# Squirco_Logic_v1_0.net
KiCad netlist of a schematic drawn in EAGLE
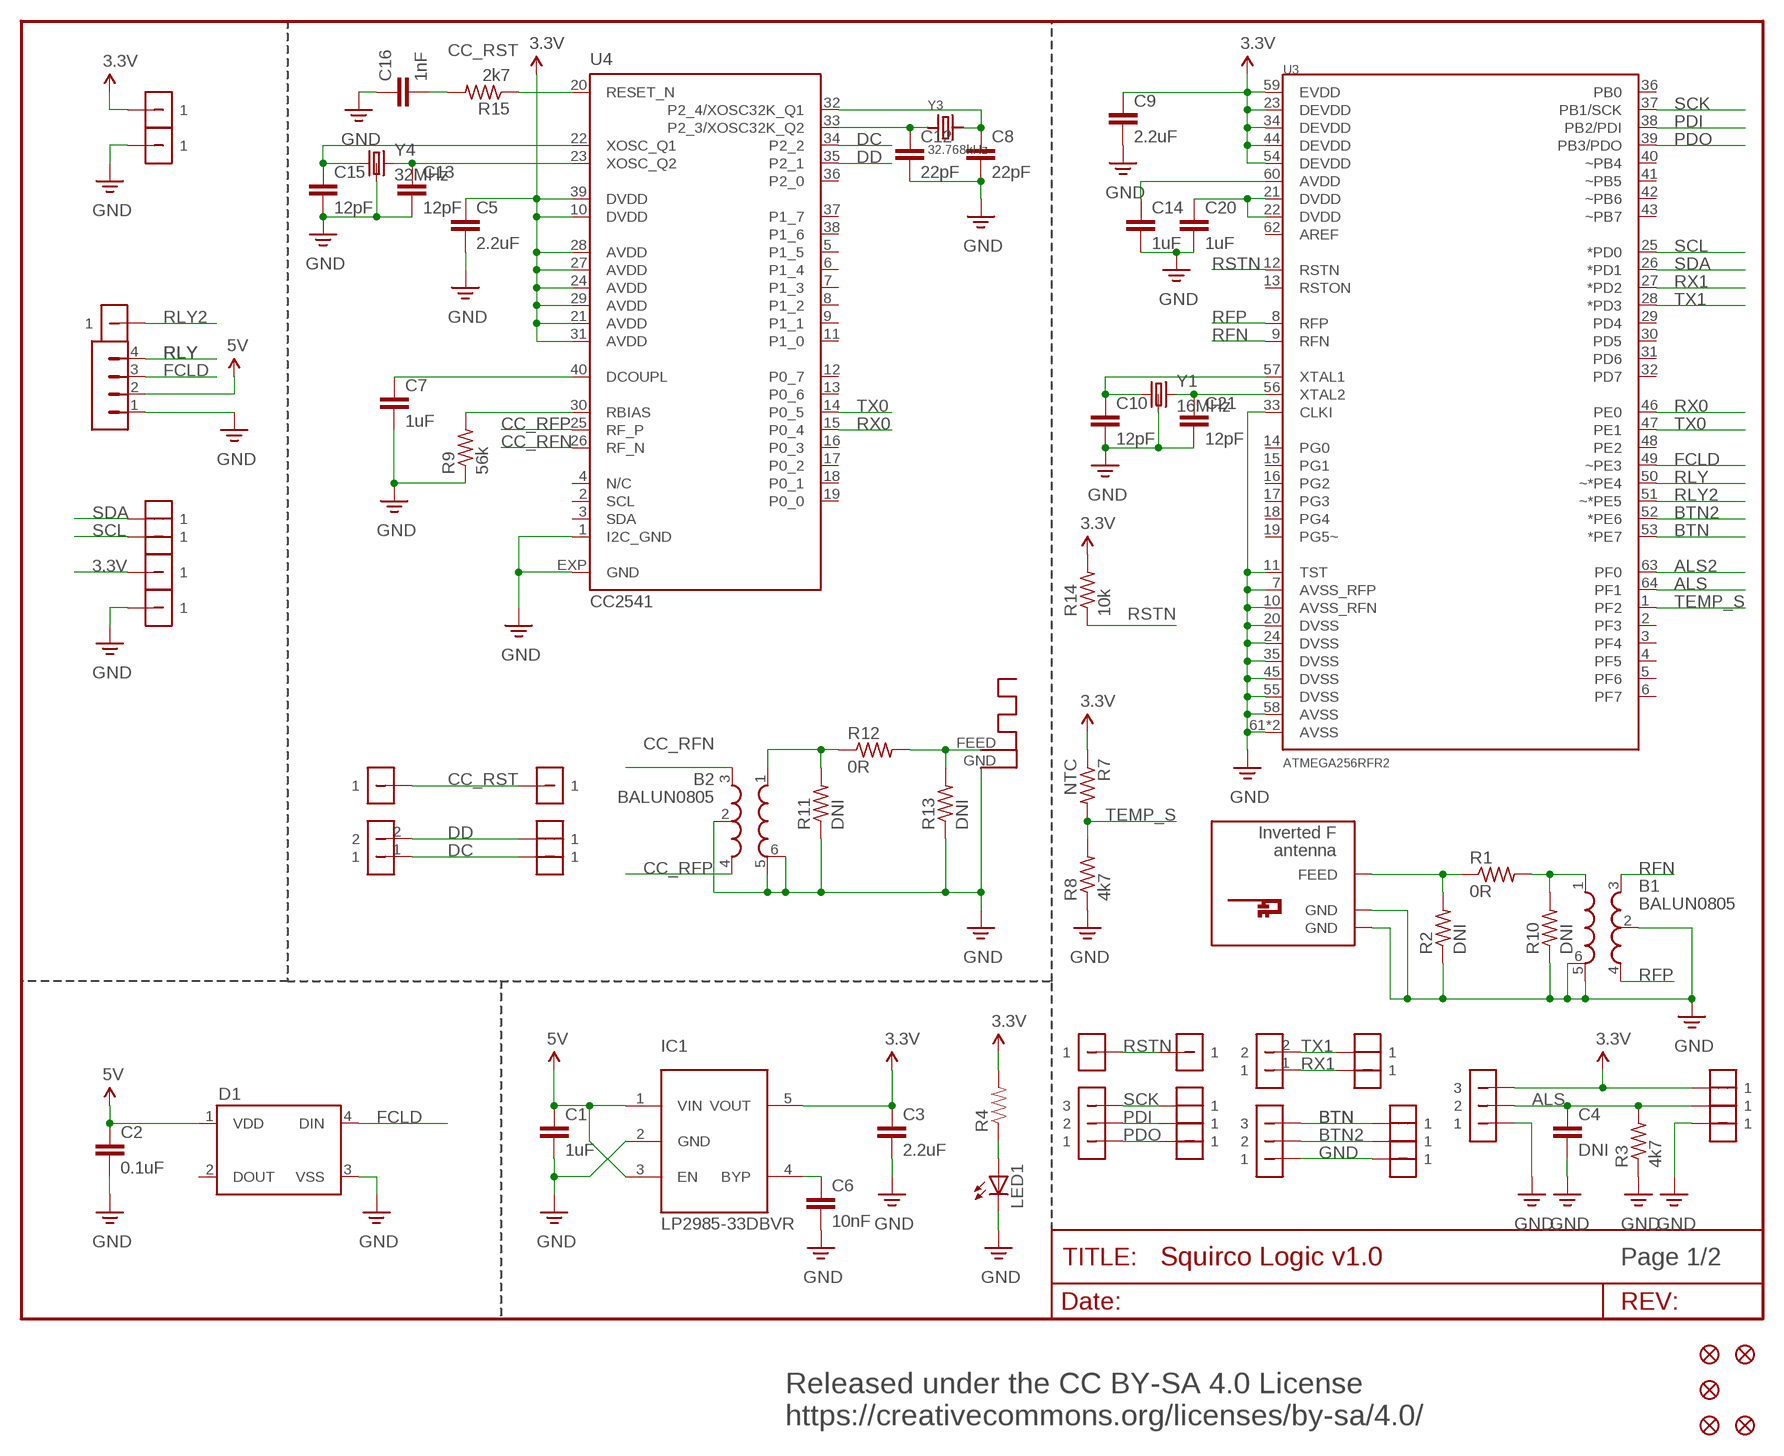
[diagram p0: schematic, sheet 1]

(export (version "E")
  (design (tool "Eeschema 10.0.6"))
  (components
    (comp (ref "ANT1")
      (value "ANTENNA")
      (footprint "eagle-import:RN-ANT")
      (libsource (lib "eagle-import") (part "ANTENNA"))
    )
    (comp (ref "ANT2")
      (value "INVERTED_F_ANTENNA+5")
      (footprint "eagle-import:DN007+5")
      (libsource (lib "eagle-import") (part "INVERTED_F_ANTENNA+5"))
    )
    (comp (ref "B1")
      (value "BALUN0805")
      (footprint "eagle-import:BALUN-2-4GHZ")
      (libsource (lib "eagle-import") (part "BALUN0805"))
    )
    (comp (ref "B2")
      (value "BALUN0805")
      (footprint "eagle-import:BALUN-2-4GHZ")
      (libsource (lib "eagle-import") (part "BALUN0805"))
    )
    (comp (ref "C1")
      (value "1uF")
      (footprint "eagle-import:0603-CAP")
      (libsource (lib "eagle-import") (part "CAP0603-CAP"))
    )
    (comp (ref "C2")
      (value "0.1uF")
      (footprint "eagle-import:0603-CAP")
      (libsource (lib "eagle-import") (part "CAP0603-CAP"))
    )
    (comp (ref "C3")
      (value "2.2uF")
      (footprint "eagle-import:0603-CAP")
      (libsource (lib "eagle-import") (part "CAP0603-CAP"))
    )
    (comp (ref "C4")
      (value "DNI")
      (footprint "eagle-import:0603-CAP")
      (libsource (lib "eagle-import") (part "CAP0603-CAP"))
    )
    (comp (ref "C5")
      (value "2.2uF")
      (footprint "eagle-import:0603-CAP")
      (libsource (lib "eagle-import") (part "CAP0603-CAP"))
    )
    (comp (ref "C6")
      (value "10nF")
      (footprint "eagle-import:0603-CAP")
      (libsource (lib "eagle-import") (part "CAP0603-CAP"))
    )
    (comp (ref "C7")
      (value "1uF")
      (footprint "eagle-import:0603-CAP")
      (libsource (lib "eagle-import") (part "CAP0603-CAP"))
    )
    (comp (ref "C8")
      (value "22pF")
      (footprint "eagle-import:0402-CAP")
      (libsource (lib "eagle-import") (part "CAP0402-CAP"))
    )
    (comp (ref "C9")
      (value "2.2uF")
      (footprint "eagle-import:0603-CAP")
      (libsource (lib "eagle-import") (part "CAP0603-CAP"))
    )
    (comp (ref "C10")
      (value "12pF")
      (footprint "eagle-import:0402-CAP")
      (libsource (lib "eagle-import") (part "CAP0402-CAP"))
    )
    (comp (ref "C12")
      (value "22pF")
      (footprint "eagle-import:0402-CAP")
      (libsource (lib "eagle-import") (part "CAP0402-CAP"))
    )
    (comp (ref "C13")
      (value "12pF")
      (footprint "eagle-import:0402-CAP")
      (libsource (lib "eagle-import") (part "CAP0402-CAP"))
    )
    (comp (ref "C14")
      (value "1uF")
      (footprint "eagle-import:0603-CAP")
      (libsource (lib "eagle-import") (part "CAP0603-CAP"))
    )
    (comp (ref "C15")
      (value "12pF")
      (footprint "eagle-import:0402-CAP")
      (libsource (lib "eagle-import") (part "CAP0402-CAP"))
    )
    (comp (ref "C16")
      (value "1nF")
      (footprint "eagle-import:0603-CAP")
      (libsource (lib "eagle-import") (part "CAP0603-CAP"))
    )
    (comp (ref "C20")
      (value "1uF")
      (footprint "eagle-import:0603-CAP")
      (libsource (lib "eagle-import") (part "CAP0603-CAP"))
    )
    (comp (ref "C21")
      (value "12pF")
      (footprint "eagle-import:0402-CAP")
      (libsource (lib "eagle-import") (part "CAP0402-CAP"))
    )
    (comp (ref "D1")
      (value "WS2812B")
      (footprint "eagle-import:WS2812B")
      (libsource (lib "eagle-import") (part "WS2812B"))
    )
    (comp (ref "FID1")
      (value "FIDUCIALUFIDUCIAL")
      (footprint "eagle-import:MICRO-FIDUCIAL")
      (libsource (lib "eagle-import") (part "FIDUCIALUFIDUCIAL"))
    )
    (comp (ref "FID2")
      (value "FIDUCIALUFIDUCIAL")
      (footprint "eagle-import:MICRO-FIDUCIAL")
      (libsource (lib "eagle-import") (part "FIDUCIALUFIDUCIAL"))
    )
    (comp (ref "FID3")
      (value "FIDUCIALUFIDUCIAL")
      (footprint "eagle-import:MICRO-FIDUCIAL")
      (libsource (lib "eagle-import") (part "FIDUCIALUFIDUCIAL"))
    )
    (comp (ref "FID5")
      (value "FIDUCIALUFIDUCIAL")
      (footprint "eagle-import:MICRO-FIDUCIAL")
      (libsource (lib "eagle-import") (part "FIDUCIALUFIDUCIAL"))
    )
    (comp (ref "FID6")
      (value "FIDUCIALUFIDUCIAL")
      (footprint "eagle-import:MICRO-FIDUCIAL")
      (libsource (lib "eagle-import") (part "FIDUCIALUFIDUCIAL"))
    )
    (comp (ref "IC1")
      (value "LP2985-33DBVR")
      (footprint "eagle-import:SOT23-5L")
      (libsource (lib "eagle-import") (part "LP298XS"))
    )
    (comp (ref "JP1")
      (value "M02")
      (footprint "eagle-import:M02")
      (libsource (lib "eagle-import") (part "M02"))
    )
    (comp (ref "LED1")
      (value "LEDCHIP-LED0805")
      (footprint "eagle-import:CHIP-LED0805")
      (libsource (lib "eagle-import") (part "LEDCHIP-LED0805"))
    )
    (comp (ref "R1")
      (value "0R")
      (footprint "eagle-import:R0402")
      (libsource (lib "eagle-import") (part "R-US_R0402"))
    )
    (comp (ref "R2")
      (value "DNI")
      (footprint "eagle-import:R0402")
      (libsource (lib "eagle-import") (part "R-US_R0402"))
    )
    (comp (ref "R3")
      (value "4k7")
      (footprint "eagle-import:R0603")
      (libsource (lib "eagle-import") (part "R-US_R0603"))
    )
    (comp (ref "R4")
      (value "RESISTOR0603")
      (footprint "eagle-import:0603-RES")
      (libsource (lib "eagle-import") (part "RESISTOR0603"))
    )
    (comp (ref "R7")
      (value "NTC")
      (footprint "eagle-import:R0402")
      (libsource (lib "eagle-import") (part "R-US_R0402"))
    )
    (comp (ref "R8")
      (value "4k7")
      (footprint "eagle-import:R0603")
      (libsource (lib "eagle-import") (part "R-US_R0603"))
    )
    (comp (ref "R9")
      (value "56k")
      (footprint "eagle-import:R0603")
      (libsource (lib "eagle-import") (part "R-US_R0603"))
    )
    (comp (ref "R10")
      (value "DNI")
      (footprint "eagle-import:R0402")
      (libsource (lib "eagle-import") (part "R-US_R0402"))
    )
    (comp (ref "R11")
      (value "DNI")
      (footprint "eagle-import:R0402")
      (libsource (lib "eagle-import") (part "R-US_R0402"))
    )
    (comp (ref "R12")
      (value "0R")
      (footprint "eagle-import:R0402")
      (libsource (lib "eagle-import") (part "R-US_R0402"))
    )
    (comp (ref "R13")
      (value "DNI")
      (footprint "eagle-import:R0402")
      (libsource (lib "eagle-import") (part "R-US_R0402"))
    )
    (comp (ref "R14")
      (value "10k")
      (footprint "eagle-import:R0603")
      (libsource (lib "eagle-import") (part "R-US_R0603"))
    )
    (comp (ref "R15")
      (value "2k7")
      (footprint "eagle-import:R0603")
      (libsource (lib "eagle-import") (part "R-US_R0603"))
    )
    (comp (ref "U$4")
      (value "M03")
      (footprint "eagle-import:M03")
      (libsource (lib "eagle-import") (part "M03"))
    )
    (comp (ref "U$5")
      (value "S04-4MM")
      (footprint "eagle-import:S04-4MM")
      (libsource (lib "eagle-import") (part "S04-4MM"))
    )
    (comp (ref "U$6")
      (value "M03")
      (footprint "eagle-import:M03")
      (libsource (lib "eagle-import") (part "M03"))
    )
    (comp (ref "U$7")
      (value "M01")
      (footprint "eagle-import:M01")
      (libsource (lib "eagle-import") (part "M01"))
    )
    (comp (ref "U$8")
      (value "M01")
      (footprint "eagle-import:M01")
      (libsource (lib "eagle-import") (part "M01"))
    )
    (comp (ref "U$9")
      (value "M02")
      (footprint "eagle-import:M02")
      (libsource (lib "eagle-import") (part "M02"))
    )
    (comp (ref "U$10")
      (value "S01C-4MM")
      (footprint "eagle-import:S01C-4MM")
      (libsource (lib "eagle-import") (part "S01C-4MM"))
    )
    (comp (ref "U$11")
      (value "S01C-4MM")
      (footprint "eagle-import:S01C-4MM")
      (libsource (lib "eagle-import") (part "S01C-4MM"))
    )
    (comp (ref "U$12")
      (value "S01C-4MM")
      (footprint "eagle-import:S01C-4MM")
      (libsource (lib "eagle-import") (part "S01C-4MM"))
    )
    (comp (ref "U$13")
      (value "S01C-4MM")
      (footprint "eagle-import:S01C-4MM")
      (libsource (lib "eagle-import") (part "S01C-4MM"))
    )
    (comp (ref "U$14")
      (value "S01C-4MM")
      (footprint "eagle-import:S01C-4MM")
      (libsource (lib "eagle-import") (part "S01C-4MM"))
    )
    (comp (ref "U$15")
      (value "S01C-4MM")
      (footprint "eagle-import:S01C-4MM")
      (libsource (lib "eagle-import") (part "S01C-4MM"))
    )
    (comp (ref "U$16")
      (value "S01C-4MM")
      (footprint "eagle-import:S01C-4MM")
      (libsource (lib "eagle-import") (part "S01C-4MM"))
    )
    (comp (ref "U$17")
      (value "S01C-4MM")
      (footprint "eagle-import:S01C-4MM")
      (libsource (lib "eagle-import") (part "S01C-4MM"))
    )
    (comp (ref "U$18")
      (value "S01C-4MM")
      (footprint "eagle-import:S01C-4MM")
      (libsource (lib "eagle-import") (part "S01C-4MM"))
    )
    (comp (ref "U$19")
      (value "S01C-4MM")
      (footprint "eagle-import:S01C-4MM")
      (libsource (lib "eagle-import") (part "S01C-4MM"))
    )
    (comp (ref "U$20")
      (value "S01C-4MM")
      (footprint "eagle-import:S01C-4MM")
      (libsource (lib "eagle-import") (part "S01C-4MM"))
    )
    (comp (ref "U$21")
      (value "S01C-4MM")
      (footprint "eagle-import:S01C-4MM")
      (libsource (lib "eagle-import") (part "S01C-4MM"))
    )
    (comp (ref "U$22")
      (value "S01C-4MM")
      (footprint "eagle-import:S01C-4MM")
      (libsource (lib "eagle-import") (part "S01C-4MM"))
    )
    (comp (ref "U$23")
      (value "S01C-4MM")
      (footprint "eagle-import:S01C-4MM")
      (libsource (lib "eagle-import") (part "S01C-4MM"))
    )
    (comp (ref "U$24")
      (value "S01C-4MM")
      (footprint "eagle-import:S01C-4MM")
      (libsource (lib "eagle-import") (part "S01C-4MM"))
    )
    (comp (ref "U$25")
      (value "M03")
      (footprint "eagle-import:M03")
      (libsource (lib "eagle-import") (part "M03"))
    )
    (comp (ref "U$26")
      (value "S01C-4MM")
      (footprint "eagle-import:S01C-4MM")
      (libsource (lib "eagle-import") (part "S01C-4MM"))
    )
    (comp (ref "U$27")
      (value "S01C-4MM")
      (footprint "eagle-import:S01C-4MM")
      (libsource (lib "eagle-import") (part "S01C-4MM"))
    )
    (comp (ref "U$30")
      (value "S01C-4MM")
      (footprint "eagle-import:S01C-4MM")
      (libsource (lib "eagle-import") (part "S01C-4MM"))
    )
    (comp (ref "U$31")
      (value "S01C-4MM")
      (footprint "eagle-import:S01C-4MM")
      (libsource (lib "eagle-import") (part "S01C-4MM"))
    )
    (comp (ref "U$32")
      (value "S01-4MM")
      (footprint "eagle-import:S01-4MM")
      (libsource (lib "eagle-import") (part "S01-4MM"))
    )
    (comp (ref "U$33")
      (value "S01-4MM")
      (footprint "eagle-import:S01-4MM")
      (libsource (lib "eagle-import") (part "S01-4MM"))
    )
    (comp (ref "U$34")
      (value "S01C-4MM")
      (footprint "eagle-import:S01C-4MM")
      (libsource (lib "eagle-import") (part "S01C-4MM"))
    )
    (comp (ref "U3")
      (value "ATMEGA256RFR2")
      (footprint "eagle-import:QFN-64")
      (libsource (lib "eagle-import") (part "ATMEGA256RFR2"))
    )
    (comp (ref "U4")
      (value "CC2541")
      (footprint "eagle-import:RHA_S-PVQFN-N40")
      (libsource (lib "eagle-import") (part "CC2541"))
    )
    (comp (ref "Y1")
      (value "16MHz")
      (footprint "eagle-import:CRYSTAL-SMD-2.5X2-ABM10")
      (libsource (lib "eagle-import") (part "CRYSTALABM10"))
    )
    (comp (ref "Y3")
      (value "32.768kHz")
      (footprint "eagle-import:ABS07")
      (libsource (lib "eagle-import") (part "CRYSTAL.ABS07"))
    )
    (comp (ref "Y4")
      (value "32MHz")
      (footprint "eagle-import:CRYSTAL-SMD-2.5X2-ABM10")
      (libsource (lib "eagle-import") (part "CRYSTALABM10"))
    )
  )
  (nets
    (net (code "1") (name "/ALS") (class "Default")
      (node (ref "C4") (pin "1") (pinfunction "1_1") (pintype "passive"))
      (node (ref "R3") (pin "2") (pinfunction "2_2") (pintype "passive"))
      (node (ref "U$25") (pin "2") (pinfunction "2_2") (pintype "bidirectional"))
      (node (ref "U$31") (pin "P$1") (pinfunction "1_P$1") (pintype "bidirectional"))
      (node (ref "U3") (pin "64") (pinfunction "PF1_64") (pintype "bidirectional"))
    )
    (net (code "2") (name "/ALS2") (class "Default")
      (node (ref "U3") (pin "63") (pinfunction "PF0_63") (pintype "bidirectional"))
    )
    (net (code "3") (name "/BTN") (class "Default")
      (node (ref "U$22") (pin "P$1") (pinfunction "1_P$1") (pintype "bidirectional"))
      (node (ref "U$6") (pin "3") (pinfunction "3_3") (pintype "bidirectional"))
      (node (ref "U3") (pin "53") (pinfunction "*PE7_53") (pintype "bidirectional"))
    )
    (net (code "4") (name "/BTN2") (class "Default")
      (node (ref "U$23") (pin "P$1") (pinfunction "1_P$1") (pintype "bidirectional"))
      (node (ref "U$6") (pin "2") (pinfunction "2_2") (pintype "bidirectional"))
      (node (ref "U3") (pin "52") (pinfunction "*PE6_52") (pintype "bidirectional"))
    )
    (net (code "5") (name "/CC_RFN") (class "Default")
      (node (ref "B2") (pin "3") (pinfunction "3_3") (pintype "bidirectional"))
      (node (ref "U4") (pin "26") (pinfunction "RF_N_26") (pintype "bidirectional"))
    )
    (net (code "6") (name "/CC_RFP") (class "Default")
      (node (ref "B2") (pin "4") (pinfunction "4_4") (pintype "bidirectional"))
      (node (ref "U4") (pin "25") (pinfunction "RF_P_25") (pintype "bidirectional"))
    )
    (net (code "7") (name "/CC_RST") (class "Default")
      (node (ref "C16") (pin "2") (pinfunction "2_2") (pintype "passive"))
      (node (ref "R15") (pin "2") (pinfunction "2_2") (pintype "passive"))
      (node (ref "U$17") (pin "P$1") (pinfunction "1_P$1") (pintype "bidirectional"))
      (node (ref "U$8") (pin "1") (pinfunction "1_1") (pintype "bidirectional"))
    )
    (net (code "8") (name "/DC") (class "Default")
      (node (ref "U$19") (pin "P$1") (pinfunction "1_P$1") (pintype "bidirectional"))
      (node (ref "U$9") (pin "1") (pinfunction "1_1") (pintype "bidirectional"))
      (node (ref "U4") (pin "34") (pinfunction "P2_2_34") (pintype "bidirectional"))
    )
    (net (code "9") (name "/DD") (class "Default")
      (node (ref "U$18") (pin "P$1") (pinfunction "1_P$1") (pintype "bidirectional"))
      (node (ref "U$9") (pin "2") (pinfunction "2_2") (pintype "bidirectional"))
      (node (ref "U4") (pin "35") (pinfunction "P2_1_35") (pintype "bidirectional"))
    )
    (net (code "10") (name "/FCLD") (class "Default")
      (node (ref "D1") (pin "4") (pinfunction "DIN_4") (pintype "input"))
      (node (ref "U$5") (pin "3") (pinfunction "3_3") (pintype "bidirectional"))
      (node (ref "U3") (pin "49") (pinfunction "~{PE3}_49") (pintype "bidirectional"))
    )
    (net (code "11") (name "/N{slash}C") (class "Default")
      (node (ref "U4") (pin "4") (pinfunction "N/C_4") (pintype "power_in"))
    )
    (net (code "12") (name "/PDI") (class "Default")
      (node (ref "U$13") (pin "P$1") (pinfunction "1_P$1") (pintype "bidirectional"))
      (node (ref "U$4") (pin "2") (pinfunction "2_2") (pintype "bidirectional"))
      (node (ref "U3") (pin "38") (pinfunction "PB2/PDI_38") (pintype "bidirectional"))
    )
    (net (code "13") (name "/PDO") (class "Default")
      (node (ref "U$14") (pin "P$1") (pinfunction "1_P$1") (pintype "bidirectional"))
      (node (ref "U$4") (pin "1") (pinfunction "1_1") (pintype "bidirectional"))
      (node (ref "U3") (pin "39") (pinfunction "PB3/PDO_39") (pintype "bidirectional"))
    )
    (net (code "14") (name "/RFN") (class "Default")
      (node (ref "B1") (pin "3") (pinfunction "3_3") (pintype "bidirectional"))
      (node (ref "U3") (pin "9") (pinfunction "RFN_9") (pintype "bidirectional"))
    )
    (net (code "15") (name "/RFP") (class "Default")
      (node (ref "B1") (pin "4") (pinfunction "4_4") (pintype "bidirectional"))
      (node (ref "U3") (pin "8") (pinfunction "RFP_8") (pintype "bidirectional"))
    )
    (net (code "16") (name "/RLY") (class "Default")
      (node (ref "U$5") (pin "4") (pinfunction "4_4") (pintype "bidirectional"))
      (node (ref "U3") (pin "50") (pinfunction "~{*PE4}_50") (pintype "bidirectional"))
    )
    (net (code "17") (name "/RLY2") (class "Default")
      (node (ref "U$34") (pin "P$1") (pinfunction "1_P$1") (pintype "bidirectional"))
      (node (ref "U3") (pin "51") (pinfunction "~{*PE5}_51") (pintype "bidirectional"))
    )
    (net (code "18") (name "/RSTN") (class "Default")
      (node (ref "R14") (pin "1") (pinfunction "1_1") (pintype "passive"))
      (node (ref "U$11") (pin "P$1") (pinfunction "1_P$1") (pintype "bidirectional"))
      (node (ref "U$7") (pin "1") (pinfunction "1_1") (pintype "bidirectional"))
      (node (ref "U3") (pin "12") (pinfunction "RSTN_12") (pintype "bidirectional"))
    )
    (net (code "19") (name "/RX0") (class "Default")
      (node (ref "U3") (pin "46") (pinfunction "PE0_46") (pintype "bidirectional"))
      (node (ref "U4") (pin "15") (pinfunction "P0_4_15") (pintype "bidirectional"))
    )
    (net (code "20") (name "/RX1") (class "Default")
      (node (ref "JP1") (pin "1") (pinfunction "1_1") (pintype "bidirectional"))
      (node (ref "U$16") (pin "P$1") (pinfunction "1_P$1") (pintype "bidirectional"))
      (node (ref "U3") (pin "27") (pinfunction "*PD2_27") (pintype "bidirectional"))
    )
    (net (code "21") (name "/SCK") (class "Default")
      (node (ref "U$12") (pin "P$1") (pinfunction "1_P$1") (pintype "bidirectional"))
      (node (ref "U$4") (pin "3") (pinfunction "3_3") (pintype "bidirectional"))
      (node (ref "U3") (pin "37") (pinfunction "PB1/SCK_37") (pintype "bidirectional"))
    )
    (net (code "22") (name "/SCL") (class "Default")
      (node (ref "U$24") (pin "P$1") (pinfunction "1_P$1") (pintype "bidirectional"))
      (node (ref "U3") (pin "25") (pinfunction "*PD0_25") (pintype "bidirectional"))
    )
    (net (code "23") (name "/SDA") (class "Default")
      (node (ref "U$10") (pin "P$1") (pinfunction "1_P$1") (pintype "bidirectional"))
      (node (ref "U3") (pin "26") (pinfunction "*PD1_26") (pintype "bidirectional"))
    )
    (net (code "24") (name "/TEMP_S") (class "Default")
      (node (ref "R7") (pin "2") (pinfunction "2_2") (pintype "passive"))
      (node (ref "R8") (pin "2") (pinfunction "2_2") (pintype "passive"))
      (node (ref "U3") (pin "1") (pinfunction "PF2_1") (pintype "bidirectional"))
    )
    (net (code "25") (name "/TX0") (class "Default")
      (node (ref "U3") (pin "47") (pinfunction "PE1_47") (pintype "bidirectional"))
      (node (ref "U4") (pin "14") (pinfunction "P0_5_14") (pintype "bidirectional"))
    )
    (net (code "26") (name "/TX1") (class "Default")
      (node (ref "JP1") (pin "2") (pinfunction "2_2") (pintype "bidirectional"))
      (node (ref "U$15") (pin "P$1") (pinfunction "1_P$1") (pintype "bidirectional"))
      (node (ref "U3") (pin "28") (pinfunction "*PD3_28") (pintype "bidirectional"))
    )
    (net (code "27") (name "3.3V") (class "Default")
      (node (ref "C3") (pin "1") (pinfunction "1_1") (pintype "passive"))
      (node (ref "C5") (pin "1") (pinfunction "1_1") (pintype "passive"))
      (node (ref "C9") (pin "1") (pinfunction "1_1") (pintype "passive"))
      (node (ref "IC1") (pin "5") (pinfunction "VOUT_5") (pintype "bidirectional"))
      (node (ref "R14") (pin "2") (pinfunction "2_2") (pintype "passive"))
      (node (ref "R4") (pin "2") (pinfunction "2_2") (pintype "passive"))
      (node (ref "R7") (pin "1") (pinfunction "1_1") (pintype "passive"))
      (node (ref "U$20") (pin "P$1") (pinfunction "1_P$1") (pintype "bidirectional"))
      (node (ref "U$25") (pin "3") (pinfunction "3_3") (pintype "bidirectional"))
      (node (ref "U$26") (pin "P$1") (pinfunction "1_P$1") (pintype "bidirectional"))
      (node (ref "U$30") (pin "P$1") (pinfunction "1_P$1") (pintype "bidirectional"))
      (node (ref "U3") (pin "23") (pinfunction "DEVDD_23") (pintype "bidirectional"))
      (node (ref "U3") (pin "34") (pinfunction "DEVDD_34") (pintype "bidirectional"))
      (node (ref "U3") (pin "44") (pinfunction "DEVDD_44") (pintype "bidirectional"))
      (node (ref "U3") (pin "54") (pinfunction "DEVDD_54") (pintype "bidirectional"))
      (node (ref "U3") (pin "59") (pinfunction "EVDD_59") (pintype "bidirectional"))
      (node (ref "U4") (pin "10") (pinfunction "DVDD_10") (pintype "power_in"))
      (node (ref "U4") (pin "21") (pinfunction "AVDD_21") (pintype "power_in"))
      (node (ref "U4") (pin "24") (pinfunction "AVDD_24") (pintype "power_in"))
      (node (ref "U4") (pin "27") (pinfunction "AVDD_27") (pintype "power_in"))
      (node (ref "U4") (pin "28") (pinfunction "AVDD_28") (pintype "power_in"))
      (node (ref "U4") (pin "29") (pinfunction "AVDD_29") (pintype "power_in"))
      (node (ref "U4") (pin "31") (pinfunction "AVDD_31") (pintype "power_in"))
      (node (ref "U4") (pin "39") (pinfunction "DVDD_39") (pintype "power_in"))
    )
    (net (code "28") (name "5V") (class "Default")
      (node (ref "C1") (pin "1") (pinfunction "1_1") (pintype "passive"))
      (node (ref "C2") (pin "1") (pinfunction "1_1") (pintype "passive"))
      (node (ref "D1") (pin "1") (pinfunction "VDD_1") (pintype "power_in"))
      (node (ref "IC1") (pin "1") (pinfunction "VIN_1") (pintype "bidirectional"))
      (node (ref "IC1") (pin "3") (pinfunction "EN_3") (pintype "bidirectional"))
      (node (ref "U$5") (pin "2") (pinfunction "2_2") (pintype "bidirectional"))
    )
    (net (code "29") (name "GND") (class "Default")
      (node (ref "ANT1") (pin "GND") (pinfunction "GND_GND") (pintype "passive"))
      (node (ref "ANT2") (pin "GND") (pinfunction "GND_GND") (pintype "bidirectional"))
      (node (ref "ANT2") (pin "GND@1") (pinfunction "GND_GND@1") (pintype "bidirectional"))
      (node (ref "B1") (pin "2") (pinfunction "2_2") (pintype "bidirectional"))
      (node (ref "B1") (pin "5") (pinfunction "5_5") (pintype "bidirectional"))
      (node (ref "B1") (pin "6") (pinfunction "6_6") (pintype "bidirectional"))
      (node (ref "B2") (pin "2") (pinfunction "2_2") (pintype "bidirectional"))
      (node (ref "B2") (pin "5") (pinfunction "5_5") (pintype "bidirectional"))
      (node (ref "B2") (pin "6") (pinfunction "6_6") (pintype "bidirectional"))
      (node (ref "C1") (pin "2") (pinfunction "2_2") (pintype "passive"))
      (node (ref "C10") (pin "2") (pinfunction "2_2") (pintype "passive"))
      (node (ref "C12") (pin "2") (pinfunction "2_2") (pintype "passive"))
      (node (ref "C13") (pin "2") (pinfunction "2_2") (pintype "passive"))
      (node (ref "C14") (pin "2") (pinfunction "2_2") (pintype "passive"))
      (node (ref "C15") (pin "2") (pinfunction "2_2") (pintype "passive"))
      (node (ref "C16") (pin "1") (pinfunction "1_1") (pintype "passive"))
      (node (ref "C2") (pin "2") (pinfunction "2_2") (pintype "passive"))
      (node (ref "C20") (pin "2") (pinfunction "2_2") (pintype "passive"))
      (node (ref "C21") (pin "2") (pinfunction "2_2") (pintype "passive"))
      (node (ref "C3") (pin "2") (pinfunction "2_2") (pintype "passive"))
      (node (ref "C4") (pin "2") (pinfunction "2_2") (pintype "passive"))
      (node (ref "C5") (pin "2") (pinfunction "2_2") (pintype "passive"))
      (node (ref "C6") (pin "2") (pinfunction "2_2") (pintype "passive"))
      (node (ref "C7") (pin "2") (pinfunction "2_2") (pintype "passive"))
      (node (ref "C8") (pin "2") (pinfunction "2_2") (pintype "passive"))
      (node (ref "C9") (pin "2") (pinfunction "2_2") (pintype "passive"))
      (node (ref "D1") (pin "3") (pinfunction "VSS_3") (pintype "power_in"))
      (node (ref "IC1") (pin "2") (pinfunction "GND_2") (pintype "bidirectional"))
      (node (ref "LED1") (pin "C") (pinfunction "C_C") (pintype "passive"))
      (node (ref "R10") (pin "1") (pinfunction "1_1") (pintype "passive"))
      (node (ref "R11") (pin "1") (pinfunction "1_1") (pintype "passive"))
      (node (ref "R13") (pin "1") (pinfunction "1_1") (pintype "passive"))
      (node (ref "R2") (pin "1") (pinfunction "1_1") (pintype "passive"))
      (node (ref "R3") (pin "1") (pinfunction "1_1") (pintype "passive"))
      (node (ref "R8") (pin "1") (pinfunction "1_1") (pintype "passive"))
      (node (ref "R9") (pin "1") (pinfunction "1_1") (pintype "passive"))
      (node (ref "U$21") (pin "P$1") (pinfunction "1_P$1") (pintype "bidirectional"))
      (node (ref "U$25") (pin "1") (pinfunction "1_1") (pintype "bidirectional"))
      (node (ref "U$27") (pin "P$1") (pinfunction "1_P$1") (pintype "bidirectional"))
      (node (ref "U$32") (pin "P$1") (pinfunction "1_P$1") (pintype "bidirectional"))
      (node (ref "U$33") (pin "P$1") (pinfunction "1_P$1") (pintype "bidirectional"))
      (node (ref "U$5") (pin "1") (pinfunction "1_1") (pintype "bidirectional"))
      (node (ref "U$6") (pin "1") (pinfunction "1_1") (pintype "bidirectional"))
      (node (ref "U3") (pin "10") (pinfunction "AVSS_RFN_10") (pintype "bidirectional"))
      (node (ref "U3") (pin "11") (pinfunction "TST_11") (pintype "bidirectional"))
      (node (ref "U3") (pin "20") (pinfunction "DVSS_20") (pintype "bidirectional"))
      (node (ref "U3") (pin "24") (pinfunction "DVSS_24") (pintype "bidirectional"))
      (node (ref "U3") (pin "33") (pinfunction "CLKI_33") (pintype "bidirectional"))
      (node (ref "U3") (pin "35") (pinfunction "DVSS_35") (pintype "bidirectional"))
      (node (ref "U3") (pin "45") (pinfunction "DVSS_45") (pintype "bidirectional"))
      (node (ref "U3") (pin "55") (pinfunction "DVSS_55") (pintype "bidirectional"))
      (node (ref "U3") (pin "58") (pinfunction "AVSS_58") (pintype "bidirectional"))
      (node (ref "U3") (pin "61") (pinfunction "AVSS_61") (pintype "bidirectional"))
      (node (ref "U3") (pin "7") (pinfunction "AVSS_RFP_7") (pintype "bidirectional"))
      (node (ref "U3") (pin "PADDLE") (pinfunction "AVSS_PADDLE") (pintype "bidirectional"))
      (node (ref "U4") (pin "1") (pinfunction "I2C_GND_1") (pintype "power_in"))
      (node (ref "U4") (pin "EXP") (pinfunction "GND_EXP") (pintype "passive"))
      (node (ref "Y1") (pin "P$2") (pinfunction "GND_P$2") (pintype "bidirectional"))
      (node (ref "Y1") (pin "P$4") (pinfunction "GND_P$4") (pintype "bidirectional"))
      (node (ref "Y4") (pin "P$2") (pinfunction "GND_P$2") (pintype "bidirectional"))
      (node (ref "Y4") (pin "P$4") (pinfunction "GND_P$4") (pintype "bidirectional"))
    )
    (net (code "30") (name "Net-(ANT1-PadFEED)") (class "Default")
      (node (ref "ANT1") (pin "FEED") (pinfunction "FEED_FEED") (pintype "passive"))
      (node (ref "R12") (pin "2") (pinfunction "2_2") (pintype "passive"))
      (node (ref "R13") (pin "2") (pinfunction "2_2") (pintype "passive"))
    )
    (net (code "31") (name "Net-(ANT2-PadFEED)") (class "Default")
      (node (ref "ANT2") (pin "FEED") (pinfunction "FEED_FEED") (pintype "bidirectional"))
      (node (ref "R1") (pin "1") (pinfunction "1_1") (pintype "passive"))
      (node (ref "R2") (pin "2") (pinfunction "2_2") (pintype "passive"))
    )
    (net (code "32") (name "Net-(B1-Pad1)") (class "Default")
      (node (ref "B1") (pin "1") (pinfunction "1_1") (pintype "bidirectional"))
      (node (ref "R1") (pin "2") (pinfunction "2_2") (pintype "passive"))
      (node (ref "R10") (pin "2") (pinfunction "2_2") (pintype "passive"))
    )
    (net (code "33") (name "Net-(B2-Pad1)") (class "Default")
      (node (ref "B2") (pin "1") (pinfunction "1_1") (pintype "bidirectional"))
      (node (ref "R11") (pin "2") (pinfunction "2_2") (pintype "passive"))
      (node (ref "R12") (pin "1") (pinfunction "1_1") (pintype "passive"))
    )
    (net (code "34") (name "Net-(C20-Pad1)") (class "Default")
      (node (ref "C20") (pin "1") (pinfunction "1_1") (pintype "passive"))
      (node (ref "U3") (pin "21") (pinfunction "DVDD_21") (pintype "bidirectional"))
      (node (ref "U3") (pin "22") (pinfunction "DVDD_22") (pintype "bidirectional"))
    )
    (net (code "35") (name "Net-(IC1-BYP)") (class "Default")
      (node (ref "C6") (pin "1") (pinfunction "1_1") (pintype "passive"))
      (node (ref "IC1") (pin "4") (pinfunction "BYP_4") (pintype "bidirectional"))
    )
    (net (code "36") (name "Net-(LED1-PadA)") (class "Default")
      (node (ref "LED1") (pin "A") (pinfunction "A_A") (pintype "passive"))
      (node (ref "R4") (pin "1") (pinfunction "1_1") (pintype "passive"))
    )
    (net (code "37") (name "Net-(U3-AVDD)") (class "Default")
      (node (ref "C14") (pin "1") (pinfunction "1_1") (pintype "passive"))
      (node (ref "U3") (pin "60") (pinfunction "AVDD_60") (pintype "bidirectional"))
    )
    (net (code "38") (name "Net-(U3-XTAL1)") (class "Default")
      (node (ref "C10") (pin "1") (pinfunction "1_1") (pintype "passive"))
      (node (ref "U3") (pin "57") (pinfunction "XTAL1_57") (pintype "bidirectional"))
      (node (ref "Y1") (pin "P$1") (pinfunction "1_P$1") (pintype "passive"))
    )
    (net (code "39") (name "Net-(U3-XTAL2)") (class "Default")
      (node (ref "C21") (pin "1") (pinfunction "1_1") (pintype "passive"))
      (node (ref "U3") (pin "56") (pinfunction "XTAL2_56") (pintype "bidirectional"))
      (node (ref "Y1") (pin "P$3") (pinfunction "2_P$3") (pintype "passive"))
    )
    (net (code "40") (name "Net-(U4-DCOUPL)") (class "Default")
      (node (ref "C7") (pin "1") (pinfunction "1_1") (pintype "passive"))
      (node (ref "U4") (pin "40") (pinfunction "DCOUPL_40") (pintype "power_in"))
    )
    (net (code "41") (name "Net-(U4-P2_3{slash}XOSC32K_Q2)") (class "Default")
      (node (ref "C12") (pin "1") (pinfunction "1_1") (pintype "passive"))
      (node (ref "U4") (pin "33") (pinfunction "P2_3/XOSC32K_Q2_33") (pintype "bidirectional"))
      (node (ref "Y3") (pin "1") (pinfunction "1_1") (pintype "passive"))
    )
    (net (code "42") (name "Net-(U4-P2_4{slash}XOSC32K_Q1)") (class "Default")
      (node (ref "C8") (pin "1") (pinfunction "1_1") (pintype "passive"))
      (node (ref "U4") (pin "32") (pinfunction "P2_4/XOSC32K_Q1_32") (pintype "bidirectional"))
      (node (ref "Y3") (pin "2") (pinfunction "2_2") (pintype "passive"))
    )
    (net (code "43") (name "Net-(U4-RBIAS)") (class "Default")
      (node (ref "R9") (pin "2") (pinfunction "2_2") (pintype "passive"))
      (node (ref "U4") (pin "30") (pinfunction "RBIAS_30") (pintype "bidirectional"))
    )
    (net (code "44") (name "Net-(U4-RESET_N)") (class "Default")
      (node (ref "R15") (pin "1") (pinfunction "1_1") (pintype "passive"))
      (node (ref "U4") (pin "20") (pinfunction "RESET_N_20") (pintype "input"))
    )
    (net (code "45") (name "Net-(U4-XOSC_Q1)") (class "Default")
      (node (ref "C15") (pin "1") (pinfunction "1_1") (pintype "passive"))
      (node (ref "U4") (pin "22") (pinfunction "XOSC_Q1_22") (pintype "bidirectional"))
      (node (ref "Y4") (pin "P$1") (pinfunction "1_P$1") (pintype "passive"))
    )
    (net (code "46") (name "Net-(U4-XOSC_Q2)") (class "Default")
      (node (ref "C13") (pin "1") (pinfunction "1_1") (pintype "passive"))
      (node (ref "U4") (pin "23") (pinfunction "XOSC_Q2_23") (pintype "bidirectional"))
      (node (ref "Y4") (pin "P$3") (pinfunction "2_P$3") (pintype "passive"))
    )
    (net (code "47") (name "unconnected-(D1-DOUT-Pad2)") (class "Default")
      (node (ref "D1") (pin "2") (pinfunction "DOUT_2") (pintype "output"))
    )
    (net (code "48") (name "unconnected-(U3-AREF-Pad62)") (class "Default")
      (node (ref "U3") (pin "62") (pinfunction "AREF_62") (pintype "bidirectional"))
    )
    (net (code "49") (name "unconnected-(U3-PB0-Pad36)") (class "Default")
      (node (ref "U3") (pin "36") (pinfunction "PB0_36") (pintype "bidirectional"))
    )
    (net (code "50") (name "unconnected-(U3-PD4-Pad29)") (class "Default")
      (node (ref "U3") (pin "29") (pinfunction "PD4_29") (pintype "bidirectional"))
    )
    (net (code "51") (name "unconnected-(U3-PD5-Pad30)") (class "Default")
      (node (ref "U3") (pin "30") (pinfunction "PD5_30") (pintype "bidirectional"))
    )
    (net (code "52") (name "unconnected-(U3-PD6-Pad31)") (class "Default")
      (node (ref "U3") (pin "31") (pinfunction "PD6_31") (pintype "bidirectional"))
    )
    (net (code "53") (name "unconnected-(U3-PD7-Pad32)") (class "Default")
      (node (ref "U3") (pin "32") (pinfunction "PD7_32") (pintype "bidirectional"))
    )
    (net (code "54") (name "unconnected-(U3-PE2-Pad48)") (class "Default")
      (node (ref "U3") (pin "48") (pinfunction "PE2_48") (pintype "bidirectional"))
    )
    (net (code "55") (name "unconnected-(U3-PF3-Pad2)") (class "Default")
      (node (ref "U3") (pin "2") (pinfunction "PF3_2") (pintype "bidirectional"))
    )
    (net (code "56") (name "unconnected-(U3-PF4-Pad3)") (class "Default")
      (node (ref "U3") (pin "3") (pinfunction "PF4_3") (pintype "bidirectional"))
    )
    (net (code "57") (name "unconnected-(U3-PF5-Pad4)") (class "Default")
      (node (ref "U3") (pin "4") (pinfunction "PF5_4") (pintype "bidirectional"))
    )
    (net (code "58") (name "unconnected-(U3-PF6-Pad5)") (class "Default")
      (node (ref "U3") (pin "5") (pinfunction "PF6_5") (pintype "bidirectional"))
    )
    (net (code "59") (name "unconnected-(U3-PF7-Pad6)") (class "Default")
      (node (ref "U3") (pin "6") (pinfunction "PF7_6") (pintype "bidirectional"))
    )
    (net (code "60") (name "unconnected-(U3-PG0-Pad14)") (class "Default")
      (node (ref "U3") (pin "14") (pinfunction "PG0_14") (pintype "bidirectional"))
    )
    (net (code "61") (name "unconnected-(U3-PG1-Pad15)") (class "Default")
      (node (ref "U3") (pin "15") (pinfunction "PG1_15") (pintype "bidirectional"))
    )
    (net (code "62") (name "unconnected-(U3-PG2-Pad16)") (class "Default")
      (node (ref "U3") (pin "16") (pinfunction "PG2_16") (pintype "bidirectional"))
    )
    (net (code "63") (name "unconnected-(U3-PG3-Pad17)") (class "Default")
      (node (ref "U3") (pin "17") (pinfunction "PG3_17") (pintype "bidirectional"))
    )
    (net (code "64") (name "unconnected-(U3-PG4-Pad18)") (class "Default")
      (node (ref "U3") (pin "18") (pinfunction "PG4_18") (pintype "bidirectional"))
    )
    (net (code "65") (name "unconnected-(U3-PG5~{}-Pad19)") (class "Default")
      (node (ref "U3") (pin "19") (pinfunction "PG5~{}_19") (pintype "bidirectional"))
    )
    (net (code "66") (name "unconnected-(U3-RSTON-Pad13)") (class "Default")
      (node (ref "U3") (pin "13") (pinfunction "RSTON_13") (pintype "bidirectional"))
    )
    (net (code "67") (name "unconnected-(U3-~{PB4}-Pad40)") (class "Default")
      (node (ref "U3") (pin "40") (pinfunction "~{PB4}_40") (pintype "bidirectional"))
    )
    (net (code "68") (name "unconnected-(U3-~{PB5}-Pad41)") (class "Default")
      (node (ref "U3") (pin "41") (pinfunction "~{PB5}_41") (pintype "bidirectional"))
    )
    (net (code "69") (name "unconnected-(U3-~{PB6}-Pad42)") (class "Default")
      (node (ref "U3") (pin "42") (pinfunction "~{PB6}_42") (pintype "bidirectional"))
    )
    (net (code "70") (name "unconnected-(U3-~{PB7}-Pad43)") (class "Default")
      (node (ref "U3") (pin "43") (pinfunction "~{PB7}_43") (pintype "bidirectional"))
    )
    (net (code "71") (name "unconnected-(U4-P0_0-Pad19)") (class "Default")
      (node (ref "U4") (pin "19") (pinfunction "P0_0_19") (pintype "bidirectional"))
    )
    (net (code "72") (name "unconnected-(U4-P0_1-Pad18)") (class "Default")
      (node (ref "U4") (pin "18") (pinfunction "P0_1_18") (pintype "bidirectional"))
    )
    (net (code "73") (name "unconnected-(U4-P0_2-Pad17)") (class "Default")
      (node (ref "U4") (pin "17") (pinfunction "P0_2_17") (pintype "bidirectional"))
    )
    (net (code "74") (name "unconnected-(U4-P0_3-Pad16)") (class "Default")
      (node (ref "U4") (pin "16") (pinfunction "P0_3_16") (pintype "bidirectional"))
    )
    (net (code "75") (name "unconnected-(U4-P0_6-Pad13)") (class "Default")
      (node (ref "U4") (pin "13") (pinfunction "P0_6_13") (pintype "bidirectional"))
    )
    (net (code "76") (name "unconnected-(U4-P0_7-Pad12)") (class "Default")
      (node (ref "U4") (pin "12") (pinfunction "P0_7_12") (pintype "bidirectional"))
    )
    (net (code "77") (name "unconnected-(U4-P1_0-Pad11)") (class "Default")
      (node (ref "U4") (pin "11") (pinfunction "P1_0_11") (pintype "bidirectional"))
    )
    (net (code "78") (name "unconnected-(U4-P1_1-Pad9)") (class "Default")
      (node (ref "U4") (pin "9") (pinfunction "P1_1_9") (pintype "bidirectional"))
    )
    (net (code "79") (name "unconnected-(U4-P1_2-Pad8)") (class "Default")
      (node (ref "U4") (pin "8") (pinfunction "P1_2_8") (pintype "bidirectional"))
    )
    (net (code "80") (name "unconnected-(U4-P1_3-Pad7)") (class "Default")
      (node (ref "U4") (pin "7") (pinfunction "P1_3_7") (pintype "bidirectional"))
    )
    (net (code "81") (name "unconnected-(U4-P1_4-Pad6)") (class "Default")
      (node (ref "U4") (pin "6") (pinfunction "P1_4_6") (pintype "bidirectional"))
    )
    (net (code "82") (name "unconnected-(U4-P1_5-Pad5)") (class "Default")
      (node (ref "U4") (pin "5") (pinfunction "P1_5_5") (pintype "bidirectional"))
    )
    (net (code "83") (name "unconnected-(U4-P1_6-Pad38)") (class "Default")
      (node (ref "U4") (pin "38") (pinfunction "P1_6_38") (pintype "bidirectional"))
    )
    (net (code "84") (name "unconnected-(U4-P1_7-Pad37)") (class "Default")
      (node (ref "U4") (pin "37") (pinfunction "P1_7_37") (pintype "bidirectional"))
    )
    (net (code "85") (name "unconnected-(U4-P2_0-Pad36)") (class "Default")
      (node (ref "U4") (pin "36") (pinfunction "P2_0_36") (pintype "bidirectional"))
    )
    (net (code "86") (name "unconnected-(U4-SCL-Pad2)") (class "Default")
      (node (ref "U4") (pin "2") (pinfunction "SCL_2") (pintype "bidirectional"))
    )
    (net (code "87") (name "unconnected-(U4-SDA-Pad3)") (class "Default")
      (node (ref "U4") (pin "3") (pinfunction "SDA_3") (pintype "bidirectional"))
    )
  )
)
